# 2channelrelaydriver_throughole.net
KiCad netlist of a schematic drawn in EAGLE
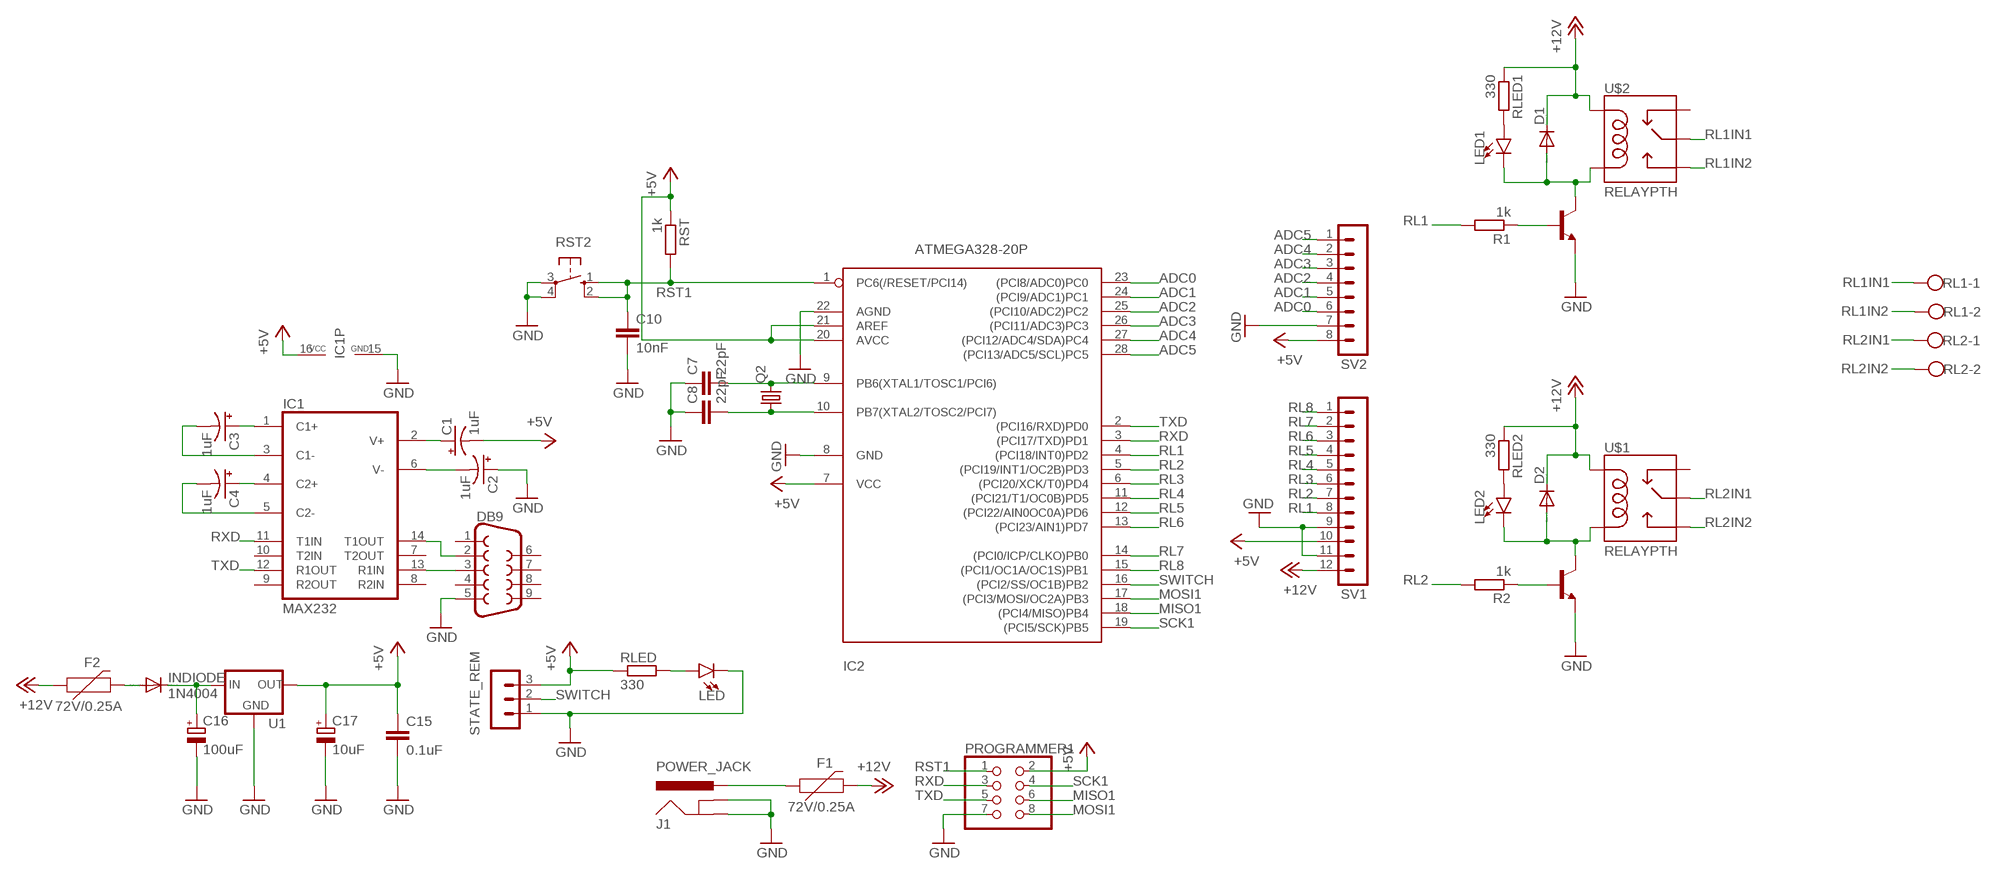
[diagram p0: schematic, sheet 1]

(export (version "E")
  (design (tool "Eeschema 10.0.6"))
  (components
    (comp (ref "C1")
      (value "1uF")
      (footprint "eagle-import:E2,5-6")
      (libsource (lib "eagle-import") (part "CPOL-USE2.5-6"))
    )
    (comp (ref "C2")
      (value "1uF")
      (footprint "eagle-import:E2,5-6")
      (libsource (lib "eagle-import") (part "CPOL-USE2.5-6"))
    )
    (comp (ref "C3")
      (value "1uF")
      (footprint "eagle-import:E2,5-6")
      (libsource (lib "eagle-import") (part "CPOL-USE2.5-6"))
    )
    (comp (ref "C4")
      (value "1uF")
      (footprint "eagle-import:E2,5-6")
      (libsource (lib "eagle-import") (part "CPOL-USE2.5-6"))
    )
    (comp (ref "C7")
      (value "22pF")
      (footprint "eagle-import:C025-025X050")
      (libsource (lib "eagle-import") (part "C-EU025-025X050"))
    )
    (comp (ref "C8")
      (value "22pF")
      (footprint "eagle-import:C025-025X050")
      (libsource (lib "eagle-import") (part "C-EU025-025X050"))
    )
    (comp (ref "C10")
      (value "10nF")
      (footprint "eagle-import:C050-025X075")
      (libsource (lib "eagle-import") (part "C-EU050-025X075"))
    )
    (comp (ref "C15")
      (value "0.1uF")
      (footprint "eagle-import:C050-025X075")
      (libsource (lib "eagle-import") (part "C-EU050-025X075"))
    )
    (comp (ref "C16")
      (value "100uF")
      (footprint "eagle-import:E2,5-6")
      (libsource (lib "eagle-import") (part "CPOL-EUE2.5-6"))
    )
    (comp (ref "C17")
      (value "10uF")
      (footprint "eagle-import:E2,5-6")
      (libsource (lib "eagle-import") (part "CPOL-EUE2.5-6"))
    )
    (comp (ref "D1")
      (value "1N4004")
      (footprint "eagle-import:DO41-10")
      (libsource (lib "eagle-import") (part "1N4004"))
    )
    (comp (ref "D2")
      (value "1N4004")
      (footprint "eagle-import:DO41-10")
      (libsource (lib "eagle-import") (part "1N4004"))
    )
    (comp (ref "DB9")
      (value "DB9FEMALE")
      (footprint "eagle-import:DB9")
      (libsource (lib "eagle-import") (part "DB9FEMALE"))
    )
    (comp (ref "F1")
      (value "72V/0.25A")
      (footprint "eagle-import:PTH")
      (libsource (lib "eagle-import") (part "PPTC_PTH"))
    )
    (comp (ref "F2")
      (value "72V/0.25A")
      (footprint "eagle-import:PTH")
      (libsource (lib "eagle-import") (part "PPTC_PTH"))
    )
    (comp (ref "IC1")
      (value "MAX232")
      (footprint "eagle-import:DIL16")
      (fields (field (name "MF") "MAXIM") (field (name "MPN") "MAX232ACPE+"))
      (libsource (lib "eagle-import") (part "MAX232"))
    )
    (comp (ref "IC2")
      (value "ATMEGA328-20P")
      (footprint "eagle-import:DIL28-3")
      (libsource (lib "eagle-import") (part "ATMEGA328P-20"))
    )
    (comp (ref "INDIODE")
      (value "1N4004")
      (footprint "eagle-import:DO41-10")
      (libsource (lib "eagle-import") (part "1N4004"))
    )
    (comp (ref "J1")
      (value "POWER_JACK")
      (footprint "eagle-import:POWER_JACK_PTH")
      (libsource (lib "eagle-import") (part "POWER_JACK"))
    )
    (comp (ref "LED")
      (value "LED5MM")
      (footprint "eagle-import:LED_5MM")
      (libsource (lib "eagle-import") (part "LED5MM"))
    )
    (comp (ref "LED1")
      (value "LED5MM")
      (footprint "eagle-import:LED_5MM")
      (libsource (lib "eagle-import") (part "LED5MM"))
    )
    (comp (ref "LED2")
      (value "LED5MM")
      (footprint "eagle-import:LED_5MM")
      (libsource (lib "eagle-import") (part "LED5MM"))
    )
    (comp (ref "PROGRAMMER1")
      (value "PINHD-2X4")
      (footprint "eagle-import:2X04")
      (libsource (lib "eagle-import") (part "PINHD-2X4"))
    )
    (comp (ref "Q2")
      (value "CRYSTALHC49U70")
      (footprint "eagle-import:HC49U70")
      (libsource (lib "eagle-import") (part "CRYSTALHC49U70"))
    )
    (comp (ref "R1")
      (value "1k")
      (footprint "eagle-import:0207_10")
      (libsource (lib "eagle-import") (part "R-EU_0207/10"))
    )
    (comp (ref "R2")
      (value "1k")
      (footprint "eagle-import:0207_10")
      (libsource (lib "eagle-import") (part "R-EU_0207/10"))
    )
    (comp (ref "RL1")
      (value "W237-102")
      (footprint "eagle-import:W237-102")
      (fields (field (name "MPN") "237-102"))
      (libsource (lib "eagle-import") (part "W237-102"))
    )
    (comp (ref "RL2")
      (value "W237-102")
      (footprint "eagle-import:W237-102")
      (fields (field (name "MPN") "237-102"))
      (libsource (lib "eagle-import") (part "W237-102"))
    )
    (comp (ref "RLED")
      (value "330")
      (footprint "eagle-import:0207_10")
      (libsource (lib "eagle-import") (part "R-EU_0207/10"))
    )
    (comp (ref "RLED1")
      (value "330")
      (footprint "eagle-import:0207_10")
      (libsource (lib "eagle-import") (part "R-EU_0207/10"))
    )
    (comp (ref "RLED2")
      (value "330")
      (footprint "eagle-import:0207_10")
      (libsource (lib "eagle-import") (part "R-EU_0207/10"))
    )
    (comp (ref "RST")
      (value "1k")
      (footprint "eagle-import:0207_10")
      (libsource (lib "eagle-import") (part "R-EU_0207/10"))
    )
    (comp (ref "RST2")
      (value "10-XX")
      (footprint "eagle-import:B3F-10XX")
      (fields (field (name "MPN") "B3F-1000"))
      (libsource (lib "eagle-import") (part "10-XX"))
    )
    (comp (ref "STATE_REM")
      (value "MA03-1")
      (footprint "eagle-import:MA03-1")
      (libsource (lib "eagle-import") (part "MA03-1"))
    )
    (comp (ref "SV1")
      (value "MA12-1")
      (footprint "eagle-import:MA12-1")
      (libsource (lib "eagle-import") (part "MA12-1"))
    )
    (comp (ref "SV2")
      (value "MA08-1")
      (footprint "eagle-import:MA08-1")
      (libsource (lib "eagle-import") (part "MA08-1"))
    )
    (comp (ref "T1")
      (value "BC547")
      (footprint "eagle-import:TO92")
      (libsource (lib "eagle-import") (part "BC547"))
    )
    (comp (ref "T2")
      (value "BC547")
      (footprint "eagle-import:TO92")
      (libsource (lib "eagle-import") (part "BC547"))
    )
    (comp (ref "U$1")
      (value "RELAYPTH")
      (footprint "eagle-import:SRD-05VDC-SL-C")
      (libsource (lib "eagle-import") (part "RELAYPTH"))
    )
    (comp (ref "U$2")
      (value "RELAYPTH")
      (footprint "eagle-import:SRD-05VDC-SL-C")
      (libsource (lib "eagle-import") (part "RELAYPTH"))
    )
    (comp (ref "U1")
      (value "V_REG_78XXSIDE")
      (footprint "eagle-import:78XXL")
      (libsource (lib "eagle-import") (part "V_REG_78XXSIDE"))
    )
  )
  (nets
    (net (code "1") (name "+5V") (class "Default")
      (node (ref "C1") (pin "-") (pinfunction "-_-") (pintype "passive"))
      (node (ref "C15") (pin "1") (pinfunction "1_1") (pintype "passive"))
      (node (ref "C17") (pin "+") (pinfunction "+_+") (pintype "passive"))
      (node (ref "IC1") (pin "16") (pinfunction "VCC_16") (pintype "power_in"))
      (node (ref "IC2") (pin "20") (pinfunction "AVCC_20") (pintype "bidirectional"))
      (node (ref "IC2") (pin "21") (pinfunction "AREF_21") (pintype "bidirectional"))
      (node (ref "IC2") (pin "7") (pinfunction "VCC_7") (pintype "bidirectional"))
      (node (ref "PROGRAMMER1") (pin "2") (pinfunction "2_2") (pintype "passive"))
      (node (ref "RLED") (pin "1") (pinfunction "1_1") (pintype "passive"))
      (node (ref "RST") (pin "1") (pinfunction "1_1") (pintype "passive"))
      (node (ref "STATE_REM") (pin "3") (pinfunction "3_3") (pintype "passive"))
      (node (ref "SV1") (pin "10") (pinfunction "10_10") (pintype "passive"))
      (node (ref "SV2") (pin "8") (pinfunction "8_8") (pintype "passive"))
      (node (ref "U1") (pin "OUT") (pinfunction "OUT_OUT") (pintype "passive"))
    )
    (net (code "2") (name "+12V") (class "Default")
      (node (ref "D1") (pin "C") (pinfunction "C_C") (pintype "passive"))
      (node (ref "D2") (pin "C") (pinfunction "C_C") (pintype "passive"))
      (node (ref "F1") (pin "P$2") (pinfunction "2_P$2") (pintype "bidirectional"))
      (node (ref "F2") (pin "P$1") (pinfunction "1_P$1") (pintype "bidirectional"))
      (node (ref "RLED1") (pin "1") (pinfunction "1_1") (pintype "passive"))
      (node (ref "RLED2") (pin "1") (pinfunction "1_1") (pintype "passive"))
      (node (ref "SV1") (pin "12") (pinfunction "12_12") (pintype "passive"))
      (node (ref "U$1") (pin "COIL1") (pinfunction "COIL1_COIL1") (pintype "bidirectional"))
      (node (ref "U$2") (pin "COIL1") (pinfunction "COIL1_COIL1") (pintype "bidirectional"))
    )
    (net (code "3") (name "/ADC0") (class "Default")
      (node (ref "IC2") (pin "23") (pinfunction "(PCI8/ADC0)PC0_23") (pintype "bidirectional"))
      (node (ref "SV2") (pin "6") (pinfunction "6_6") (pintype "passive"))
    )
    (net (code "4") (name "/ADC1") (class "Default")
      (node (ref "IC2") (pin "24") (pinfunction "(PCI9/ADC1)PC1_24") (pintype "bidirectional"))
      (node (ref "SV2") (pin "5") (pinfunction "5_5") (pintype "passive"))
    )
    (net (code "5") (name "/ADC2") (class "Default")
      (node (ref "IC2") (pin "25") (pinfunction "(PCI10/ADC2)PC2_25") (pintype "bidirectional"))
      (node (ref "SV2") (pin "4") (pinfunction "4_4") (pintype "passive"))
    )
    (net (code "6") (name "/ADC3") (class "Default")
      (node (ref "IC2") (pin "26") (pinfunction "(PCI11/ADC3)PC3_26") (pintype "bidirectional"))
      (node (ref "SV2") (pin "3") (pinfunction "3_3") (pintype "passive"))
    )
    (net (code "7") (name "/ADC4") (class "Default")
      (node (ref "IC2") (pin "27") (pinfunction "(PCI12/ADC4/SDA)PC4_27") (pintype "bidirectional"))
      (node (ref "SV2") (pin "2") (pinfunction "2_2") (pintype "passive"))
    )
    (net (code "8") (name "/ADC5") (class "Default")
      (node (ref "IC2") (pin "28") (pinfunction "(PCI13/ADC5/SCL)PC5_28") (pintype "bidirectional"))
      (node (ref "SV2") (pin "1") (pinfunction "1_1") (pintype "passive"))
    )
    (net (code "9") (name "/MISO1") (class "Default")
      (node (ref "IC2") (pin "18") (pinfunction "(PCI4/MISO)PB4_18") (pintype "bidirectional"))
      (node (ref "PROGRAMMER1") (pin "6") (pinfunction "6_6") (pintype "passive"))
    )
    (net (code "10") (name "/MOSI1") (class "Default")
      (node (ref "IC2") (pin "17") (pinfunction "(PCI3/MOSI/OC2A)PB3_17") (pintype "bidirectional"))
      (node (ref "PROGRAMMER1") (pin "8") (pinfunction "8_8") (pintype "passive"))
    )
    (net (code "11") (name "/RL1") (class "Default")
      (node (ref "IC2") (pin "4") (pinfunction "(PCI18/INT0)PD2_4") (pintype "bidirectional"))
      (node (ref "R1") (pin "2") (pinfunction "2_2") (pintype "passive"))
      (node (ref "SV1") (pin "8") (pinfunction "8_8") (pintype "passive"))
    )
    (net (code "12") (name "/RL1IN1") (class "Default")
      (node (ref "RL1") (pin "1") (pinfunction "KL_1") (pintype "passive"))
      (node (ref "U$2") (pin "SWCOMMON") (pinfunction "SWCOMMON_SWCOMMON") (pintype "bidirectional"))
    )
    (net (code "13") (name "/RL1IN2") (class "Default")
      (node (ref "RL1") (pin "2") (pinfunction "KL_2") (pintype "passive"))
      (node (ref "U$2") (pin "SWOPEN") (pinfunction "SWOPEN_SWOPEN") (pintype "bidirectional"))
    )
    (net (code "14") (name "/RL2") (class "Default")
      (node (ref "IC2") (pin "5") (pinfunction "(PCI19/INT1/OC2B)PD3_5") (pintype "bidirectional"))
      (node (ref "R2") (pin "2") (pinfunction "2_2") (pintype "passive"))
      (node (ref "SV1") (pin "7") (pinfunction "7_7") (pintype "passive"))
    )
    (net (code "15") (name "/RL2IN1") (class "Default")
      (node (ref "RL2") (pin "1") (pinfunction "KL_1") (pintype "passive"))
      (node (ref "U$1") (pin "SWCOMMON") (pinfunction "SWCOMMON_SWCOMMON") (pintype "bidirectional"))
    )
    (net (code "16") (name "/RL2IN2") (class "Default")
      (node (ref "RL2") (pin "2") (pinfunction "KL_2") (pintype "passive"))
      (node (ref "U$1") (pin "SWOPEN") (pinfunction "SWOPEN_SWOPEN") (pintype "bidirectional"))
    )
    (net (code "17") (name "/RL3") (class "Default")
      (node (ref "IC2") (pin "6") (pinfunction "(PCI20/XCK/T0)PD4_6") (pintype "bidirectional"))
      (node (ref "SV1") (pin "6") (pinfunction "6_6") (pintype "passive"))
    )
    (net (code "18") (name "/RL4") (class "Default")
      (node (ref "IC2") (pin "11") (pinfunction "(PCI21/T1/OC0B)PD5_11") (pintype "bidirectional"))
      (node (ref "SV1") (pin "5") (pinfunction "5_5") (pintype "passive"))
    )
    (net (code "19") (name "/RL5") (class "Default")
      (node (ref "IC2") (pin "12") (pinfunction "(PCI22/AIN0OC0A)PD6_12") (pintype "bidirectional"))
      (node (ref "SV1") (pin "4") (pinfunction "4_4") (pintype "passive"))
    )
    (net (code "20") (name "/RL6") (class "Default")
      (node (ref "IC2") (pin "13") (pinfunction "(PCI23/AIN1)PD7_13") (pintype "bidirectional"))
      (node (ref "SV1") (pin "3") (pinfunction "3_3") (pintype "passive"))
    )
    (net (code "21") (name "/RL7") (class "Default")
      (node (ref "IC2") (pin "14") (pinfunction "(PCI0/ICP/CLKO)PB0_14") (pintype "bidirectional"))
      (node (ref "SV1") (pin "2") (pinfunction "2_2") (pintype "passive"))
    )
    (net (code "22") (name "/RL8") (class "Default")
      (node (ref "IC2") (pin "15") (pinfunction "(PCI1/OC1A/OC1S)PB1_15") (pintype "bidirectional"))
      (node (ref "SV1") (pin "1") (pinfunction "1_1") (pintype "passive"))
    )
    (net (code "23") (name "/RST1") (class "Default")
      (node (ref "C10") (pin "1") (pinfunction "1_1") (pintype "passive"))
      (node (ref "IC2") (pin "1") (pinfunction "PC6(/RESET/PCI14)_1") (pintype "bidirectional"))
      (node (ref "PROGRAMMER1") (pin "1") (pinfunction "1_1") (pintype "passive"))
      (node (ref "RST") (pin "2") (pinfunction "2_2") (pintype "passive"))
      (node (ref "RST2") (pin "1") (pinfunction "S_1") (pintype "passive"))
      (node (ref "RST2") (pin "2") (pinfunction "S1_2") (pintype "passive"))
    )
    (net (code "24") (name "/RXD") (class "Default")
      (node (ref "IC1") (pin "11") (pinfunction "T1IN_11") (pintype "input"))
      (node (ref "IC2") (pin "3") (pinfunction "(PCI17/TXD)PD1_3") (pintype "bidirectional"))
      (node (ref "PROGRAMMER1") (pin "3") (pinfunction "3_3") (pintype "passive"))
    )
    (net (code "25") (name "/SCK1") (class "Default")
      (node (ref "IC2") (pin "19") (pinfunction "(PCI5/SCK)PB5_19") (pintype "bidirectional"))
      (node (ref "PROGRAMMER1") (pin "4") (pinfunction "4_4") (pintype "passive"))
    )
    (net (code "26") (name "/SWITCH") (class "Default")
      (node (ref "IC2") (pin "16") (pinfunction "(PCI2/SS/OC1B)PB2_16") (pintype "bidirectional"))
      (node (ref "STATE_REM") (pin "2") (pinfunction "2_2") (pintype "passive"))
    )
    (net (code "27") (name "/TXD") (class "Default")
      (node (ref "IC1") (pin "12") (pinfunction "R1OUT_12") (pintype "output"))
      (node (ref "IC2") (pin "2") (pinfunction "(PCI16/RXD)PD0_2") (pintype "bidirectional"))
      (node (ref "PROGRAMMER1") (pin "5") (pinfunction "5_5") (pintype "passive"))
    )
    (net (code "28") (name "GND") (class "Default")
      (node (ref "C10") (pin "2") (pinfunction "2_2") (pintype "passive"))
      (node (ref "C15") (pin "2") (pinfunction "2_2") (pintype "passive"))
      (node (ref "C16") (pin "-") (pinfunction "-_-") (pintype "passive"))
      (node (ref "C17") (pin "-") (pinfunction "-_-") (pintype "passive"))
      (node (ref "C2") (pin "+") (pinfunction "+_+") (pintype "passive"))
      (node (ref "C7") (pin "1") (pinfunction "1_1") (pintype "passive"))
      (node (ref "C8") (pin "1") (pinfunction "1_1") (pintype "passive"))
      (node (ref "DB9") (pin "5") (pinfunction "5_5") (pintype "passive"))
      (node (ref "IC1") (pin "15") (pinfunction "GND_15") (pintype "power_in"))
      (node (ref "IC2") (pin "22") (pinfunction "AGND_22") (pintype "bidirectional"))
      (node (ref "IC2") (pin "8") (pinfunction "GND_8") (pintype "bidirectional"))
      (node (ref "J1") (pin "GND") (pinfunction "GND_GND") (pintype "bidirectional"))
      (node (ref "J1") (pin "GNDBREAK") (pinfunction "GNDBREAK_GNDBREAK") (pintype "bidirectional"))
      (node (ref "LED") (pin "K") (pinfunction "C_K") (pintype "passive"))
      (node (ref "PROGRAMMER1") (pin "7") (pinfunction "7_7") (pintype "passive"))
      (node (ref "RST2") (pin "3") (pinfunction "P_3") (pintype "passive"))
      (node (ref "RST2") (pin "4") (pinfunction "P1_4") (pintype "passive"))
      (node (ref "STATE_REM") (pin "1") (pinfunction "1_1") (pintype "passive"))
      (node (ref "SV1") (pin "11") (pinfunction "11_11") (pintype "passive"))
      (node (ref "SV1") (pin "9") (pinfunction "9_9") (pintype "passive"))
      (node (ref "SV2") (pin "7") (pinfunction "7_7") (pintype "passive"))
      (node (ref "T1") (pin "1") (pinfunction "E_1") (pintype "passive"))
      (node (ref "T2") (pin "1") (pinfunction "E_1") (pintype "passive"))
      (node (ref "U1") (pin "GND") (pinfunction "GND_GND") (pintype "input"))
    )
    (net (code "29") (name "Net-(C16-Pad+)") (class "Default")
      (node (ref "C16") (pin "+") (pinfunction "+_+") (pintype "passive"))
      (node (ref "INDIODE") (pin "C") (pinfunction "C_C") (pintype "passive"))
      (node (ref "U1") (pin "IN") (pinfunction "IN_IN") (pintype "input"))
    )
    (net (code "30") (name "Net-(F1-1)") (class "Default")
      (node (ref "F1") (pin "P$1") (pinfunction "1_P$1") (pintype "bidirectional"))
      (node (ref "J1") (pin "PWR") (pinfunction "PWR_PWR") (pintype "bidirectional"))
    )
    (net (code "31") (name "Net-(F2-2)") (class "Default")
      (node (ref "F2") (pin "P$2") (pinfunction "2_P$2") (pintype "bidirectional"))
      (node (ref "INDIODE") (pin "A") (pinfunction "A_A") (pintype "passive"))
    )
    (net (code "32") (name "Net-(IC1A-C1+)") (class "Default")
      (node (ref "C3") (pin "+") (pinfunction "+_+") (pintype "passive"))
      (node (ref "IC1") (pin "1") (pinfunction "C1+_1") (pintype "bidirectional"))
    )
    (net (code "33") (name "Net-(IC1A-C1-)") (class "Default")
      (node (ref "C3") (pin "-") (pinfunction "-_-") (pintype "passive"))
      (node (ref "IC1") (pin "3") (pinfunction "C1-_3") (pintype "bidirectional"))
    )
    (net (code "34") (name "Net-(IC1A-C2+)") (class "Default")
      (node (ref "C4") (pin "+") (pinfunction "+_+") (pintype "passive"))
      (node (ref "IC1") (pin "4") (pinfunction "C2+_4") (pintype "bidirectional"))
    )
    (net (code "35") (name "Net-(IC1A-C2-)") (class "Default")
      (node (ref "C4") (pin "-") (pinfunction "-_-") (pintype "passive"))
      (node (ref "IC1") (pin "5") (pinfunction "C2-_5") (pintype "bidirectional"))
    )
    (net (code "36") (name "Net-(IC1A-R1IN)") (class "Default")
      (node (ref "DB9") (pin "3") (pinfunction "3_3") (pintype "passive"))
      (node (ref "IC1") (pin "13") (pinfunction "R1IN_13") (pintype "input"))
    )
    (net (code "37") (name "Net-(IC1A-T1OUT)") (class "Default")
      (node (ref "DB9") (pin "2") (pinfunction "2_2") (pintype "passive"))
      (node (ref "IC1") (pin "14") (pinfunction "T1OUT_14") (pintype "output"))
    )
    (net (code "38") (name "Net-(IC1A-V+)") (class "Default")
      (node (ref "C1") (pin "+") (pinfunction "+_+") (pintype "passive"))
      (node (ref "IC1") (pin "2") (pinfunction "V+_2") (pintype "bidirectional"))
    )
    (net (code "39") (name "Net-(IC1A-V-)") (class "Default")
      (node (ref "C2") (pin "-") (pinfunction "-_-") (pintype "passive"))
      (node (ref "IC1") (pin "6") (pinfunction "V-_6") (pintype "bidirectional"))
    )
    (net (code "40") (name "Net-(IC2-PB6(XTAL1{slash}TOSC1{slash}PCI6))") (class "Default")
      (node (ref "C7") (pin "2") (pinfunction "2_2") (pintype "passive"))
      (node (ref "IC2") (pin "9") (pinfunction "PB6(XTAL1/TOSC1/PCI6)_9") (pintype "bidirectional"))
      (node (ref "Q2") (pin "2") (pinfunction "2_2") (pintype "passive"))
    )
    (net (code "41") (name "Net-(IC2-PB7(XTAL2{slash}TOSC2{slash}PCI7))") (class "Default")
      (node (ref "C8") (pin "2") (pinfunction "2_2") (pintype "passive"))
      (node (ref "IC2") (pin "10") (pinfunction "PB7(XTAL2/TOSC2/PCI7)_10") (pintype "bidirectional"))
      (node (ref "Q2") (pin "1") (pinfunction "1_1") (pintype "passive"))
    )
    (net (code "42") (name "Net-(LED-PadA)") (class "Default")
      (node (ref "LED") (pin "A") (pinfunction "A_A") (pintype "passive"))
      (node (ref "RLED") (pin "2") (pinfunction "2_2") (pintype "passive"))
    )
    (net (code "43") (name "Net-(LED1-C)") (class "Default")
      (node (ref "D1") (pin "A") (pinfunction "A_A") (pintype "passive"))
      (node (ref "LED1") (pin "K") (pinfunction "C_K") (pintype "passive"))
      (node (ref "T1") (pin "3") (pinfunction "C_3") (pintype "passive"))
      (node (ref "U$2") (pin "COIL0") (pinfunction "COIL0_COIL0") (pintype "bidirectional"))
    )
    (net (code "44") (name "Net-(LED1-PadA)") (class "Default")
      (node (ref "LED1") (pin "A") (pinfunction "A_A") (pintype "passive"))
      (node (ref "RLED1") (pin "2") (pinfunction "2_2") (pintype "passive"))
    )
    (net (code "45") (name "Net-(LED2-C)") (class "Default")
      (node (ref "D2") (pin "A") (pinfunction "A_A") (pintype "passive"))
      (node (ref "LED2") (pin "K") (pinfunction "C_K") (pintype "passive"))
      (node (ref "T2") (pin "3") (pinfunction "C_3") (pintype "passive"))
      (node (ref "U$1") (pin "COIL0") (pinfunction "COIL0_COIL0") (pintype "bidirectional"))
    )
    (net (code "46") (name "Net-(LED2-PadA)") (class "Default")
      (node (ref "LED2") (pin "A") (pinfunction "A_A") (pintype "passive"))
      (node (ref "RLED2") (pin "2") (pinfunction "2_2") (pintype "passive"))
    )
    (net (code "47") (name "Net-(T1-B)") (class "Default")
      (node (ref "R1") (pin "1") (pinfunction "1_1") (pintype "passive"))
      (node (ref "T1") (pin "2") (pinfunction "B_2") (pintype "passive"))
    )
    (net (code "48") (name "Net-(T2-B)") (class "Default")
      (node (ref "R2") (pin "1") (pinfunction "1_1") (pintype "passive"))
      (node (ref "T2") (pin "2") (pinfunction "B_2") (pintype "passive"))
    )
    (net (code "49") (name "unconnected-(DB9-Pad1)") (class "Default")
      (node (ref "DB9") (pin "1") (pinfunction "1_1") (pintype "passive"))
    )
    (net (code "50") (name "unconnected-(DB9-Pad4)") (class "Default")
      (node (ref "DB9") (pin "4") (pinfunction "4_4") (pintype "passive"))
    )
    (net (code "51") (name "unconnected-(DB9-Pad6)") (class "Default")
      (node (ref "DB9") (pin "6") (pinfunction "6_6") (pintype "passive"))
    )
    (net (code "52") (name "unconnected-(DB9-Pad7)") (class "Default")
      (node (ref "DB9") (pin "7") (pinfunction "7_7") (pintype "passive"))
    )
    (net (code "53") (name "unconnected-(DB9-Pad8)") (class "Default")
      (node (ref "DB9") (pin "8") (pinfunction "8_8") (pintype "passive"))
    )
    (net (code "54") (name "unconnected-(DB9-Pad9)") (class "Default")
      (node (ref "DB9") (pin "9") (pinfunction "9_9") (pintype "passive"))
    )
    (net (code "55") (name "unconnected-(IC1A-R2IN-Pad8)") (class "Default")
      (node (ref "IC1") (pin "8") (pinfunction "R2IN_8") (pintype "input"))
    )
    (net (code "56") (name "unconnected-(IC1A-R2OUT-Pad9)") (class "Default")
      (node (ref "IC1") (pin "9") (pinfunction "R2OUT_9") (pintype "output"))
    )
    (net (code "57") (name "unconnected-(IC1A-T2IN-Pad10)") (class "Default")
      (node (ref "IC1") (pin "10") (pinfunction "T2IN_10") (pintype "input"))
    )
    (net (code "58") (name "unconnected-(IC1A-T2OUT-Pad7)") (class "Default")
      (node (ref "IC1") (pin "7") (pinfunction "T2OUT_7") (pintype "output"))
    )
    (net (code "59") (name "unconnected-(U$1-SWCLOSE-PadSWCLOSED)") (class "Default")
      (node (ref "U$1") (pin "SWCLOSED") (pinfunction "SWCLOSE_SWCLOSED") (pintype "bidirectional"))
    )
    (net (code "60") (name "unconnected-(U$2-SWCLOSE-PadSWCLOSED)") (class "Default")
      (node (ref "U$2") (pin "SWCLOSED") (pinfunction "SWCLOSE_SWCLOSED") (pintype "bidirectional"))
    )
  )
)
